# SCH_MPU6050_2021-10-01.net
KiCad netlist of a schematic drawn in EasyEDA
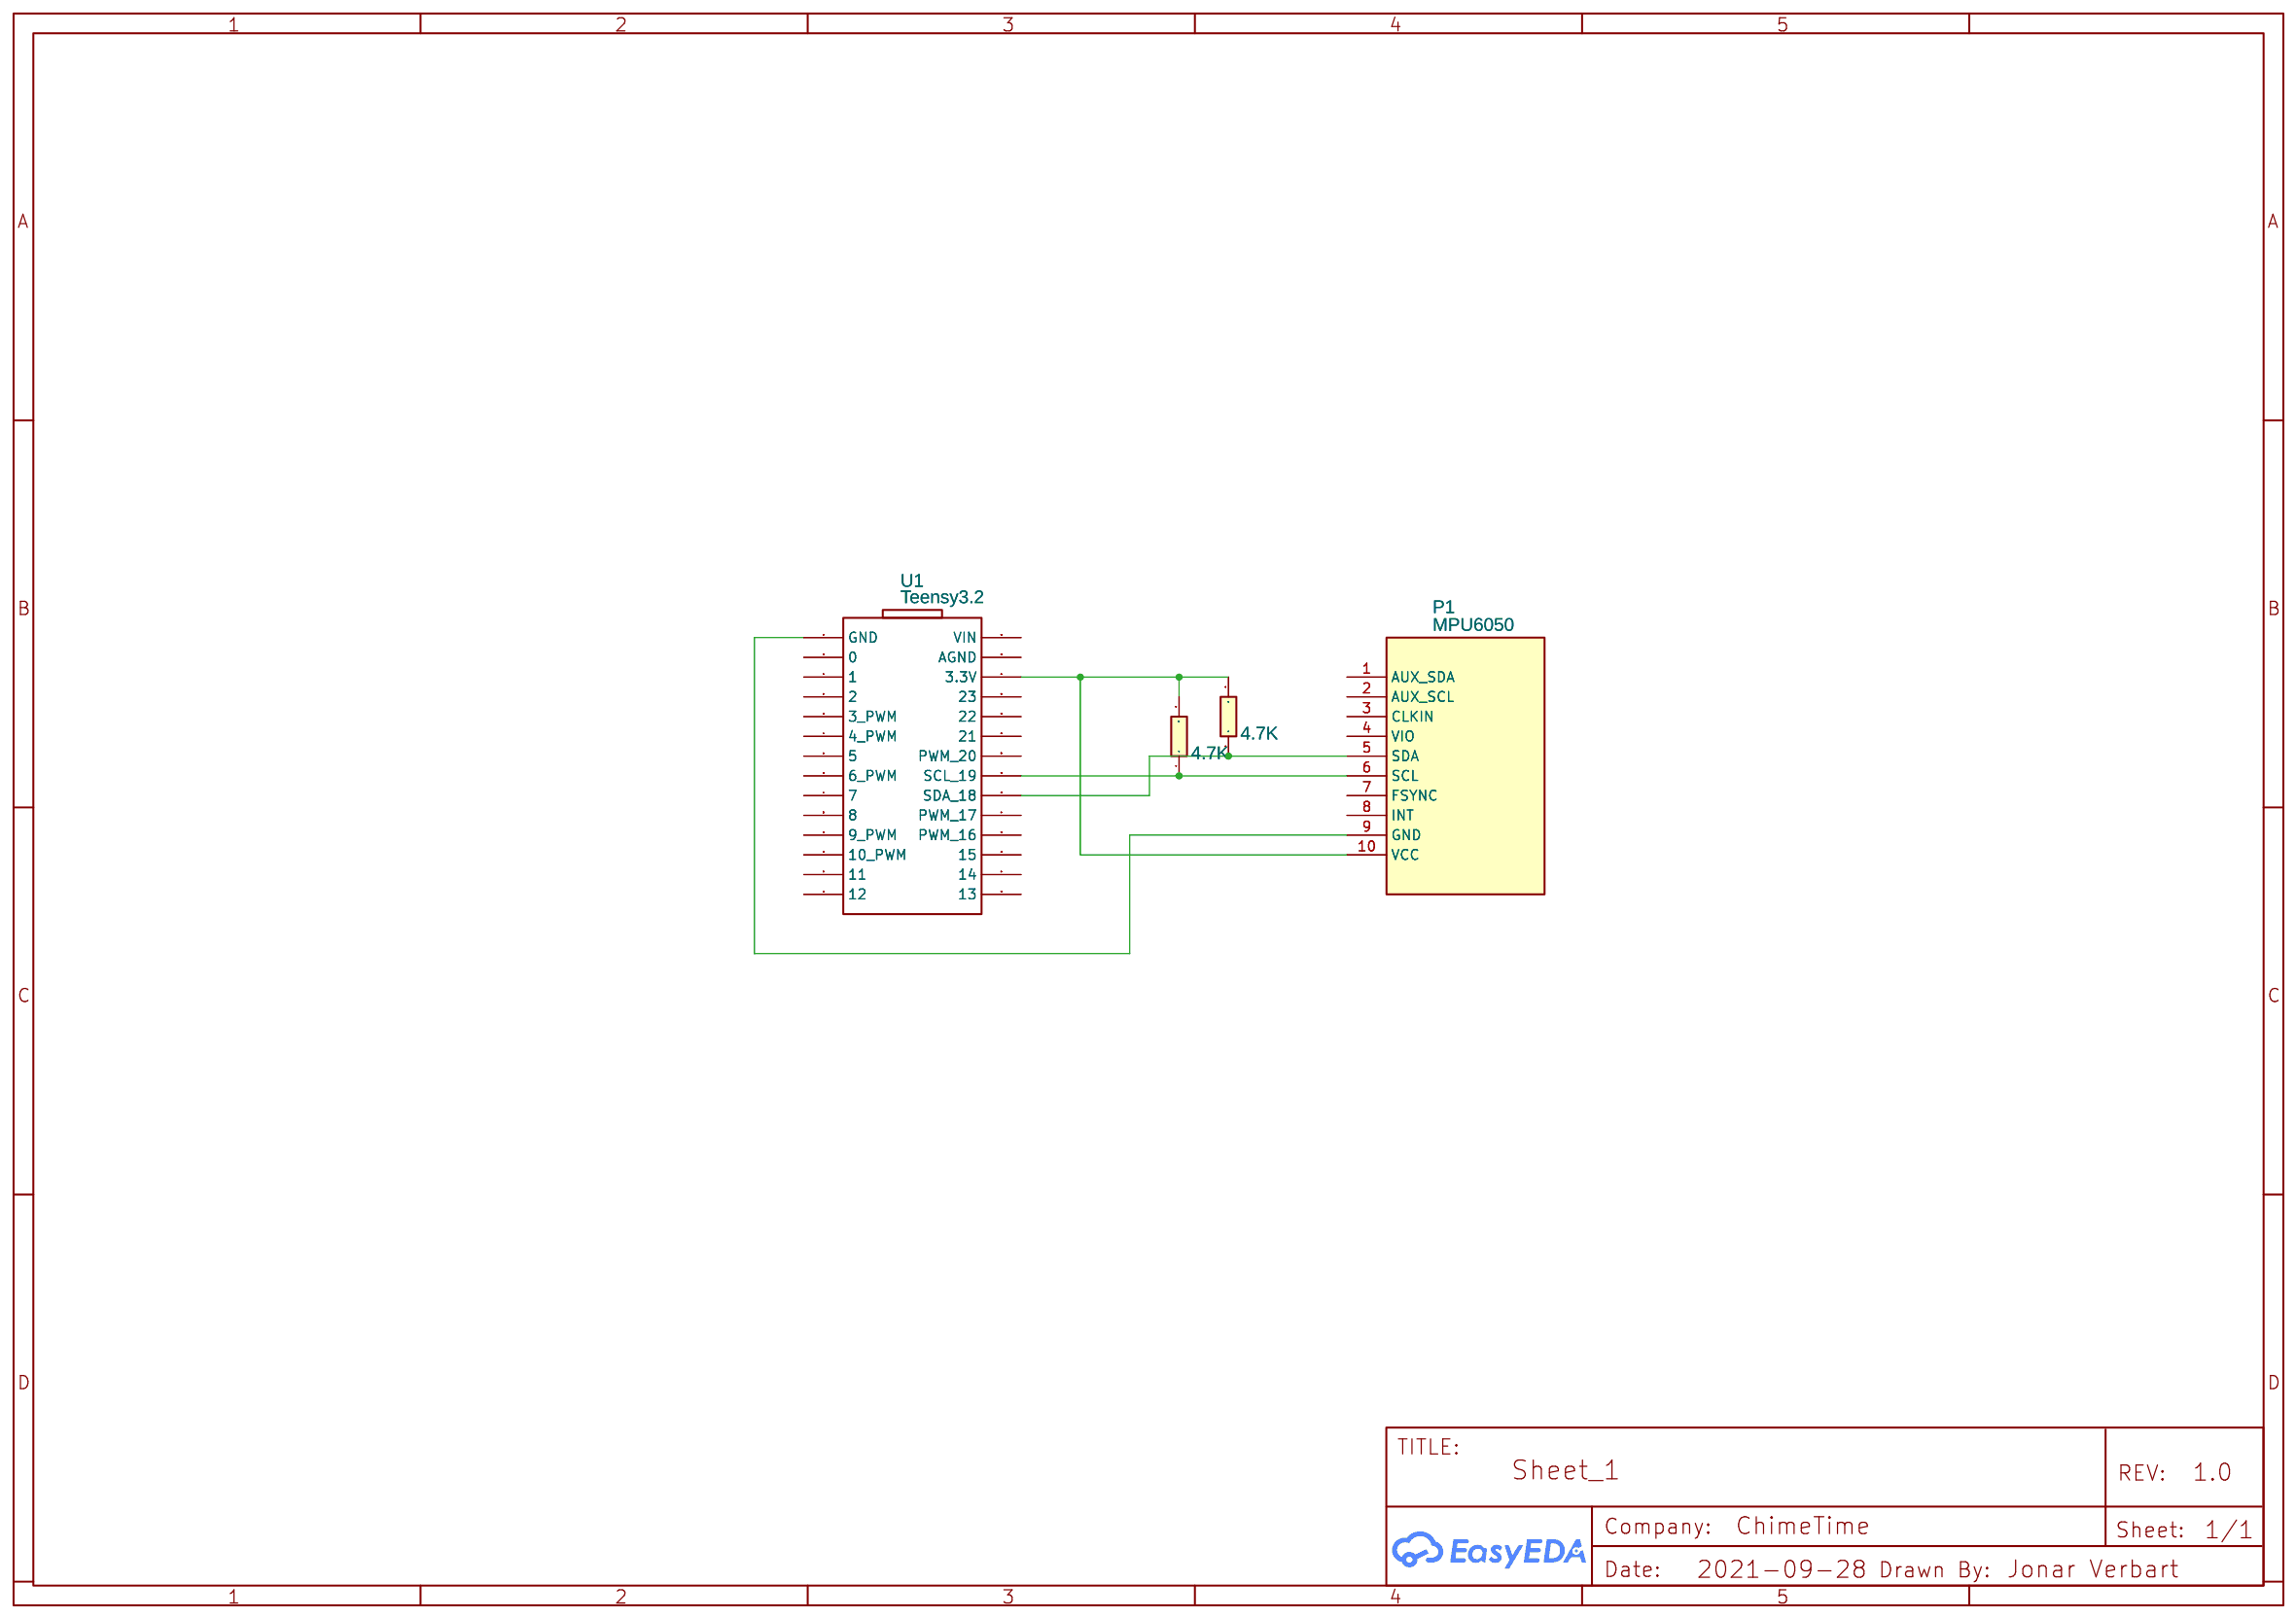
[diagram p0: schematic sheet]

(export (version "E")
  (design (tool "Eeschema 10.0.6"))
  (components
    (comp (ref "4.7K") (value "4.7K") (libsource (lib "") (part "L0603_EU")))
    (comp (ref "L2") (value "4.7K") (libsource (lib "") (part "L0603_EU_1")))
    (comp (ref "P1") (value "MPU6050") (libsource (lib "") (part "MPU6050")))
    (comp (ref "U1")
      (value "Teensy3.2")
      (fields (field (name "BOM_Manufacturer Part") "Teensy 3.2"))
      (libsource (lib "") (part "Teensy3.2"))
    )
  )
  (nets
    (net (code "1") (name "Net-(P1-GND)") (class "Default")
      (node (ref "P1") (pin "9") (pinfunction "GND_9") (pintype "unspecified"))
      (node (ref "U1") (pin "27") (pinfunction "GND_27") (pintype "unspecified"))
    )
    (net (code "2") (name "Net-(P1-SCL)") (class "Default")
      (node (ref "L2") (pin "1") (pinfunction "1_1") (pintype "unspecified"))
      (node (ref "P1") (pin "6") (pinfunction "SCL_6") (pintype "unspecified"))
      (node (ref "U1") (pin "19") (pinfunction "SCL_19_19") (pintype "unspecified"))
    )
    (net (code "3") (name "Net-(P1-SDA)") (class "Default")
      (node (ref "4.7K") (pin "1") (pinfunction "1_1") (pintype "unspecified"))
      (node (ref "P1") (pin "5") (pinfunction "SDA_5") (pintype "unspecified"))
      (node (ref "U1") (pin "18") (pinfunction "SDA_18_18") (pintype "unspecified"))
    )
    (net (code "4") (name "Net-(P1-VCC)") (class "Default")
      (node (ref "4.7K") (pin "2") (pinfunction "2_2") (pintype "unspecified"))
      (node (ref "L2") (pin "2") (pinfunction "2_2") (pintype "unspecified"))
      (node (ref "P1") (pin "10") (pinfunction "VCC_10") (pintype "unspecified"))
      (node (ref "U1") (pin "24") (pinfunction "3.3V_24") (pintype "unspecified"))
    )
    (net (code "5") (name "unconnected-(P1-AUX_SCL-Pad2)") (class "Default")
      (node (ref "P1") (pin "2") (pinfunction "AUX_SCL_2") (pintype "unspecified"))
    )
    (net (code "6") (name "unconnected-(P1-AUX_SDA-Pad1)") (class "Default")
      (node (ref "P1") (pin "1") (pinfunction "AUX_SDA_1") (pintype "unspecified"))
    )
    (net (code "7") (name "unconnected-(P1-CLKIN-Pad3)") (class "Default")
      (node (ref "P1") (pin "3") (pinfunction "CLKIN_3") (pintype "unspecified"))
    )
    (net (code "8") (name "unconnected-(P1-FSYNC-Pad7)") (class "Default")
      (node (ref "P1") (pin "7") (pinfunction "FSYNC_7") (pintype "unspecified"))
    )
    (net (code "9") (name "unconnected-(P1-INT-Pad8)") (class "Default")
      (node (ref "P1") (pin "8") (pinfunction "INT_8") (pintype "unspecified"))
    )
    (net (code "10") (name "unconnected-(P1-VIO-Pad4)") (class "Default")
      (node (ref "P1") (pin "4") (pinfunction "VIO_4") (pintype "unspecified"))
    )
    (net (code "11") (name "unconnected-(U1-3_PWM-Pad3)") (class "Default")
      (node (ref "U1") (pin "3") (pinfunction "3_PWM_3") (pintype "unspecified"))
    )
    (net (code "12") (name "unconnected-(U1-4_PWM-Pad4)") (class "Default")
      (node (ref "U1") (pin "4") (pinfunction "4_PWM_4") (pintype "unspecified"))
    )
    (net (code "13") (name "unconnected-(U1-6_PWM-Pad6)") (class "Default")
      (node (ref "U1") (pin "6") (pinfunction "6_PWM_6") (pintype "unspecified"))
    )
    (net (code "14") (name "unconnected-(U1-9_PWM-Pad9)") (class "Default")
      (node (ref "U1") (pin "9") (pinfunction "9_PWM_9") (pintype "unspecified"))
    )
    (net (code "15") (name "unconnected-(U1-10_PWM-Pad10)") (class "Default")
      (node (ref "U1") (pin "10") (pinfunction "10_PWM_10") (pintype "unspecified"))
    )
    (net (code "16") (name "unconnected-(U1-AGND-Pad25)") (class "Default")
      (node (ref "U1") (pin "25") (pinfunction "AGND_25") (pintype "unspecified"))
    )
    (net (code "17") (name "unconnected-(U1-PWM_16-Pad16)") (class "Default")
      (node (ref "U1") (pin "16") (pinfunction "PWM_16_16") (pintype "unspecified"))
    )
    (net (code "18") (name "unconnected-(U1-PWM_17-Pad17)") (class "Default")
      (node (ref "U1") (pin "17") (pinfunction "PWM_17_17") (pintype "unspecified"))
    )
    (net (code "19") (name "unconnected-(U1-PWM_20-Pad20)") (class "Default")
      (node (ref "U1") (pin "20") (pinfunction "PWM_20_20") (pintype "unspecified"))
    )
    (net (code "20") (name "unconnected-(U1-Pad0)") (class "Default")
      (node (ref "U1") (pin "0") (pinfunction "0_0") (pintype "unspecified"))
    )
    (net (code "21") (name "unconnected-(U1-Pad1)") (class "Default")
      (node (ref "U1") (pin "1") (pinfunction "1_1") (pintype "unspecified"))
    )
    (net (code "22") (name "unconnected-(U1-Pad2)") (class "Default")
      (node (ref "U1") (pin "2") (pinfunction "2_2") (pintype "unspecified"))
    )
    (net (code "23") (name "unconnected-(U1-Pad5)") (class "Default")
      (node (ref "U1") (pin "5") (pinfunction "5_5") (pintype "unspecified"))
    )
    (net (code "24") (name "unconnected-(U1-Pad7)") (class "Default")
      (node (ref "U1") (pin "7") (pinfunction "7_7") (pintype "unspecified"))
    )
    (net (code "25") (name "unconnected-(U1-Pad8)") (class "Default")
      (node (ref "U1") (pin "8") (pinfunction "8_8") (pintype "unspecified"))
    )
    (net (code "26") (name "unconnected-(U1-Pad11)") (class "Default")
      (node (ref "U1") (pin "11") (pinfunction "11_11") (pintype "unspecified"))
    )
    (net (code "27") (name "unconnected-(U1-Pad12)") (class "Default")
      (node (ref "U1") (pin "12") (pinfunction "12_12") (pintype "unspecified"))
    )
    (net (code "28") (name "unconnected-(U1-Pad13)") (class "Default")
      (node (ref "U1") (pin "13") (pinfunction "13_13") (pintype "unspecified"))
    )
    (net (code "29") (name "unconnected-(U1-Pad14)") (class "Default")
      (node (ref "U1") (pin "14") (pinfunction "14_14") (pintype "unspecified"))
    )
    (net (code "30") (name "unconnected-(U1-Pad15)") (class "Default")
      (node (ref "U1") (pin "15") (pinfunction "15_15") (pintype "unspecified"))
    )
    (net (code "31") (name "unconnected-(U1-Pad21)") (class "Default")
      (node (ref "U1") (pin "21") (pinfunction "21_21") (pintype "unspecified"))
    )
    (net (code "32") (name "unconnected-(U1-Pad22)") (class "Default")
      (node (ref "U1") (pin "22") (pinfunction "22_22") (pintype "unspecified"))
    )
    (net (code "33") (name "unconnected-(U1-Pad23)") (class "Default")
      (node (ref "U1") (pin "23") (pinfunction "23_23") (pintype "unspecified"))
    )
    (net (code "34") (name "unconnected-(U1-VIN-Pad26)") (class "Default")
      (node (ref "U1") (pin "26") (pinfunction "VIN_26") (pintype "unspecified"))
    )
  )
)
